# M101.net
KiCad netlist of a schematic drawn in EAGLE
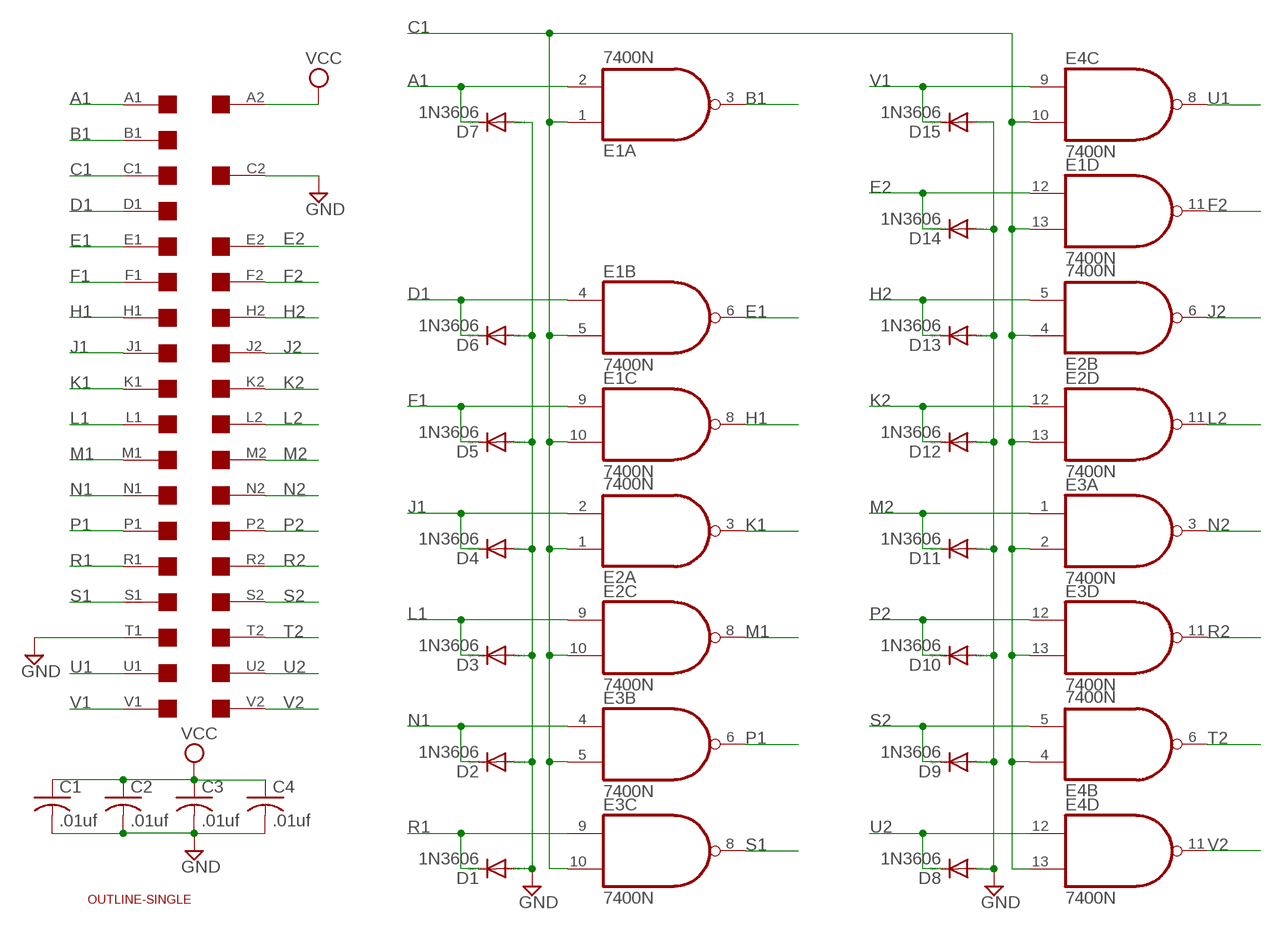
[diagram p0: schematic, sheet 1]

(export (version "E")
  (design (tool "Eeschema 10.0.6"))
  (components
    (comp (ref "C1")
      (value ".01uf")
      (footprint "eagle-import:C050-025X075")
      (libsource (lib "eagle-import") (part "C-US050-025X075"))
    )
    (comp (ref "C2")
      (value ".01uf")
      (footprint "eagle-import:C050-025X075")
      (libsource (lib "eagle-import") (part "C-US050-025X075"))
    )
    (comp (ref "C3")
      (value ".01uf")
      (footprint "eagle-import:C050-025X075")
      (libsource (lib "eagle-import") (part "C-US050-025X075"))
    )
    (comp (ref "C4")
      (value ".01uf")
      (footprint "eagle-import:C050-025X075")
      (libsource (lib "eagle-import") (part "C-US050-025X075"))
    )
    (comp (ref "D1")
      (value "1N3606")
      (footprint "eagle-import:DO35-10")
      (libsource (lib "eagle-import") (part "1N4148DO35-10"))
    )
    (comp (ref "D2")
      (value "1N3606")
      (footprint "eagle-import:DO35-10")
      (libsource (lib "eagle-import") (part "1N4148DO35-10"))
    )
    (comp (ref "D3")
      (value "1N3606")
      (footprint "eagle-import:DO35-10")
      (libsource (lib "eagle-import") (part "1N4148DO35-10"))
    )
    (comp (ref "D4")
      (value "1N3606")
      (footprint "eagle-import:DO35-10")
      (libsource (lib "eagle-import") (part "1N4148DO35-10"))
    )
    (comp (ref "D5")
      (value "1N3606")
      (footprint "eagle-import:DO35-10")
      (libsource (lib "eagle-import") (part "1N4148DO35-10"))
    )
    (comp (ref "D6")
      (value "1N3606")
      (footprint "eagle-import:DO35-10")
      (libsource (lib "eagle-import") (part "1N4148DO35-10"))
    )
    (comp (ref "D7")
      (value "1N3606")
      (footprint "eagle-import:DO35-10")
      (libsource (lib "eagle-import") (part "1N4148DO35-10"))
    )
    (comp (ref "D8")
      (value "1N3606")
      (footprint "eagle-import:DO35-10")
      (libsource (lib "eagle-import") (part "1N4148DO35-10"))
    )
    (comp (ref "D9")
      (value "1N3606")
      (footprint "eagle-import:DO35-10")
      (libsource (lib "eagle-import") (part "1N4148DO35-10"))
    )
    (comp (ref "D10")
      (value "1N3606")
      (footprint "eagle-import:DO35-10")
      (libsource (lib "eagle-import") (part "1N4148DO35-10"))
    )
    (comp (ref "D11")
      (value "1N3606")
      (footprint "eagle-import:DO35-10")
      (libsource (lib "eagle-import") (part "1N4148DO35-10"))
    )
    (comp (ref "D12")
      (value "1N3606")
      (footprint "eagle-import:DO35-10")
      (libsource (lib "eagle-import") (part "1N4148DO35-10"))
    )
    (comp (ref "D13")
      (value "1N3606")
      (footprint "eagle-import:DO35-10")
      (libsource (lib "eagle-import") (part "1N4148DO35-10"))
    )
    (comp (ref "D14")
      (value "1N3606")
      (footprint "eagle-import:DO35-10")
      (libsource (lib "eagle-import") (part "1N4148DO35-10"))
    )
    (comp (ref "D15")
      (value "1N3606")
      (footprint "eagle-import:DO35-10")
      (libsource (lib "eagle-import") (part "1N4148DO35-10"))
    )
    (comp (ref "E1")
      (value "7400N")
      (footprint "eagle-import:DIL14")
      (libsource (lib "eagle-import") (part "7400N"))
    )
    (comp (ref "E2")
      (value "7400N")
      (footprint "eagle-import:DIL14")
      (libsource (lib "eagle-import") (part "7400N"))
    )
    (comp (ref "E3")
      (value "7400N")
      (footprint "eagle-import:DIL14")
      (libsource (lib "eagle-import") (part "7400N"))
    )
    (comp (ref "E4")
      (value "7400N")
      (footprint "eagle-import:DIL14")
      (libsource (lib "eagle-import") (part "7400N"))
    )
    (comp (ref "U$1")
      (value "SINGLE")
      (footprint "eagle-import:EDGE-CON2")
      (libsource (lib "eagle-import") (part "SINGLE"))
    )
    (comp (ref "U$4")
      (value "OUTLINE-SINGLE")
      (footprint "eagle-import:SINGLE")
      (libsource (lib "eagle-import") (part "OUTLINE-SINGLE"))
    )
  )
  (nets
    (net (code "1") (name "/A1") (class "Default")
      (node (ref "D7") (pin "C") (pinfunction "C_C") (pintype "passive"))
      (node (ref "E1") (pin "2") (pinfunction "I1_2") (pintype "input"))
      (node (ref "U$1") (pin "A1") (pinfunction "1_A1") (pintype "bidirectional"))
    )
    (net (code "2") (name "/B1") (class "Default")
      (node (ref "E1") (pin "3") (pinfunction "O_3") (pintype "output"))
      (node (ref "U$1") (pin "B1") (pinfunction "1_B1") (pintype "bidirectional"))
    )
    (net (code "3") (name "/C1") (class "Default")
      (node (ref "E1") (pin "1") (pinfunction "I0_1") (pintype "input"))
      (node (ref "E1") (pin "10") (pinfunction "I1_10") (pintype "input"))
      (node (ref "E1") (pin "13") (pinfunction "I1_13") (pintype "input"))
      (node (ref "E1") (pin "5") (pinfunction "I1_5") (pintype "input"))
      (node (ref "E2") (pin "1") (pinfunction "I0_1") (pintype "input"))
      (node (ref "E2") (pin "10") (pinfunction "I1_10") (pintype "input"))
      (node (ref "E2") (pin "13") (pinfunction "I1_13") (pintype "input"))
      (node (ref "E2") (pin "4") (pinfunction "I0_4") (pintype "input"))
      (node (ref "E3") (pin "10") (pinfunction "I1_10") (pintype "input"))
      (node (ref "E3") (pin "13") (pinfunction "I1_13") (pintype "input"))
      (node (ref "E3") (pin "2") (pinfunction "I1_2") (pintype "input"))
      (node (ref "E3") (pin "5") (pinfunction "I1_5") (pintype "input"))
      (node (ref "E4") (pin "10") (pinfunction "I1_10") (pintype "input"))
      (node (ref "E4") (pin "13") (pinfunction "I1_13") (pintype "input"))
      (node (ref "E4") (pin "4") (pinfunction "I0_4") (pintype "input"))
      (node (ref "U$1") (pin "C1") (pinfunction "1_C1") (pintype "bidirectional"))
    )
    (net (code "4") (name "/D1") (class "Default")
      (node (ref "D6") (pin "C") (pinfunction "C_C") (pintype "passive"))
      (node (ref "E1") (pin "4") (pinfunction "I0_4") (pintype "input"))
      (node (ref "U$1") (pin "D1") (pinfunction "1_D1") (pintype "bidirectional"))
    )
    (net (code "5") (name "/E1") (class "Default")
      (node (ref "E1") (pin "6") (pinfunction "O_6") (pintype "output"))
      (node (ref "U$1") (pin "E1") (pinfunction "1_E1") (pintype "bidirectional"))
    )
    (net (code "6") (name "/E2") (class "Default")
      (node (ref "D14") (pin "C") (pinfunction "C_C") (pintype "passive"))
      (node (ref "E1") (pin "12") (pinfunction "I0_12") (pintype "input"))
      (node (ref "U$1") (pin "E2") (pinfunction "1_E2") (pintype "bidirectional"))
    )
    (net (code "7") (name "/F1") (class "Default")
      (node (ref "D5") (pin "C") (pinfunction "C_C") (pintype "passive"))
      (node (ref "E1") (pin "9") (pinfunction "I0_9") (pintype "input"))
      (node (ref "U$1") (pin "F1") (pinfunction "1_F1") (pintype "bidirectional"))
    )
    (net (code "8") (name "/F2") (class "Default")
      (node (ref "E1") (pin "11") (pinfunction "O_11") (pintype "output"))
      (node (ref "U$1") (pin "F2") (pinfunction "1_F2") (pintype "bidirectional"))
    )
    (net (code "9") (name "/H1") (class "Default")
      (node (ref "E1") (pin "8") (pinfunction "O_8") (pintype "output"))
      (node (ref "U$1") (pin "H1") (pinfunction "1_H1") (pintype "bidirectional"))
    )
    (net (code "10") (name "/H2") (class "Default")
      (node (ref "D13") (pin "C") (pinfunction "C_C") (pintype "passive"))
      (node (ref "E2") (pin "5") (pinfunction "I1_5") (pintype "input"))
      (node (ref "U$1") (pin "H2") (pinfunction "1_H2") (pintype "bidirectional"))
    )
    (net (code "11") (name "/J1") (class "Default")
      (node (ref "D4") (pin "C") (pinfunction "C_C") (pintype "passive"))
      (node (ref "E2") (pin "2") (pinfunction "I1_2") (pintype "input"))
      (node (ref "U$1") (pin "J1") (pinfunction "1_J1") (pintype "bidirectional"))
    )
    (net (code "12") (name "/J2") (class "Default")
      (node (ref "E2") (pin "6") (pinfunction "O_6") (pintype "output"))
      (node (ref "U$1") (pin "J2") (pinfunction "1_J2") (pintype "bidirectional"))
    )
    (net (code "13") (name "/K1") (class "Default")
      (node (ref "E2") (pin "3") (pinfunction "O_3") (pintype "output"))
      (node (ref "U$1") (pin "K1") (pinfunction "1_K1") (pintype "bidirectional"))
    )
    (net (code "14") (name "/K2") (class "Default")
      (node (ref "D12") (pin "C") (pinfunction "C_C") (pintype "passive"))
      (node (ref "E2") (pin "12") (pinfunction "I0_12") (pintype "input"))
      (node (ref "U$1") (pin "K2") (pinfunction "1_K2") (pintype "bidirectional"))
    )
    (net (code "15") (name "/L1") (class "Default")
      (node (ref "D3") (pin "C") (pinfunction "C_C") (pintype "passive"))
      (node (ref "E2") (pin "9") (pinfunction "I0_9") (pintype "input"))
      (node (ref "U$1") (pin "L1") (pinfunction "1_L1") (pintype "bidirectional"))
    )
    (net (code "16") (name "/L2") (class "Default")
      (node (ref "E2") (pin "11") (pinfunction "O_11") (pintype "output"))
      (node (ref "U$1") (pin "L2") (pinfunction "1_L2") (pintype "bidirectional"))
    )
    (net (code "17") (name "/M1") (class "Default")
      (node (ref "E2") (pin "8") (pinfunction "O_8") (pintype "output"))
      (node (ref "U$1") (pin "M1") (pinfunction "1_M1") (pintype "bidirectional"))
    )
    (net (code "18") (name "/M2") (class "Default")
      (node (ref "D11") (pin "C") (pinfunction "C_C") (pintype "passive"))
      (node (ref "E3") (pin "1") (pinfunction "I0_1") (pintype "input"))
      (node (ref "U$1") (pin "M2") (pinfunction "1_M2") (pintype "bidirectional"))
    )
    (net (code "19") (name "/N1") (class "Default")
      (node (ref "D2") (pin "C") (pinfunction "C_C") (pintype "passive"))
      (node (ref "E3") (pin "4") (pinfunction "I0_4") (pintype "input"))
      (node (ref "U$1") (pin "N1") (pinfunction "1_N1") (pintype "bidirectional"))
    )
    (net (code "20") (name "/N2") (class "Default")
      (node (ref "E3") (pin "3") (pinfunction "O_3") (pintype "output"))
      (node (ref "U$1") (pin "N2") (pinfunction "1_N2") (pintype "bidirectional"))
    )
    (net (code "21") (name "/P1") (class "Default")
      (node (ref "E3") (pin "6") (pinfunction "O_6") (pintype "output"))
      (node (ref "U$1") (pin "P1") (pinfunction "1_P1") (pintype "bidirectional"))
    )
    (net (code "22") (name "/P2") (class "Default")
      (node (ref "D10") (pin "C") (pinfunction "C_C") (pintype "passive"))
      (node (ref "E3") (pin "12") (pinfunction "I0_12") (pintype "input"))
      (node (ref "U$1") (pin "P2") (pinfunction "1_P2") (pintype "bidirectional"))
    )
    (net (code "23") (name "/R1") (class "Default")
      (node (ref "D1") (pin "C") (pinfunction "C_C") (pintype "passive"))
      (node (ref "E3") (pin "9") (pinfunction "I0_9") (pintype "input"))
      (node (ref "U$1") (pin "R1") (pinfunction "1_R1") (pintype "bidirectional"))
    )
    (net (code "24") (name "/R2") (class "Default")
      (node (ref "E3") (pin "11") (pinfunction "O_11") (pintype "output"))
      (node (ref "U$1") (pin "R2") (pinfunction "1_R2") (pintype "bidirectional"))
    )
    (net (code "25") (name "/S1") (class "Default")
      (node (ref "E3") (pin "8") (pinfunction "O_8") (pintype "output"))
      (node (ref "U$1") (pin "S1") (pinfunction "1_S1") (pintype "bidirectional"))
    )
    (net (code "26") (name "/S2") (class "Default")
      (node (ref "D9") (pin "C") (pinfunction "C_C") (pintype "passive"))
      (node (ref "E4") (pin "5") (pinfunction "I1_5") (pintype "input"))
      (node (ref "U$1") (pin "S2") (pinfunction "1_S2") (pintype "bidirectional"))
    )
    (net (code "27") (name "/T2") (class "Default")
      (node (ref "E4") (pin "6") (pinfunction "O_6") (pintype "output"))
      (node (ref "U$1") (pin "T2") (pinfunction "1_T2") (pintype "bidirectional"))
    )
    (net (code "28") (name "/U1") (class "Default")
      (node (ref "E4") (pin "8") (pinfunction "O_8") (pintype "output"))
      (node (ref "U$1") (pin "U1") (pinfunction "1_U1") (pintype "bidirectional"))
    )
    (net (code "29") (name "/U2") (class "Default")
      (node (ref "D8") (pin "C") (pinfunction "C_C") (pintype "passive"))
      (node (ref "E4") (pin "12") (pinfunction "I0_12") (pintype "input"))
      (node (ref "U$1") (pin "U2") (pinfunction "1_U2") (pintype "bidirectional"))
    )
    (net (code "30") (name "/V1") (class "Default")
      (node (ref "D15") (pin "C") (pinfunction "C_C") (pintype "passive"))
      (node (ref "E4") (pin "9") (pinfunction "I0_9") (pintype "input"))
      (node (ref "U$1") (pin "V1") (pinfunction "1_V1") (pintype "bidirectional"))
    )
    (net (code "31") (name "/V2") (class "Default")
      (node (ref "E4") (pin "11") (pinfunction "O_11") (pintype "output"))
      (node (ref "U$1") (pin "V2") (pinfunction "1_V2") (pintype "bidirectional"))
    )
    (net (code "32") (name "GND") (class "Default")
      (node (ref "C1") (pin "2") (pinfunction "2_2") (pintype "passive"))
      (node (ref "C2") (pin "2") (pinfunction "2_2") (pintype "passive"))
      (node (ref "C3") (pin "2") (pinfunction "2_2") (pintype "passive"))
      (node (ref "C4") (pin "2") (pinfunction "2_2") (pintype "passive"))
      (node (ref "D1") (pin "A") (pinfunction "A_A") (pintype "passive"))
      (node (ref "D10") (pin "A") (pinfunction "A_A") (pintype "passive"))
      (node (ref "D11") (pin "A") (pinfunction "A_A") (pintype "passive"))
      (node (ref "D12") (pin "A") (pinfunction "A_A") (pintype "passive"))
      (node (ref "D13") (pin "A") (pinfunction "A_A") (pintype "passive"))
      (node (ref "D14") (pin "A") (pinfunction "A_A") (pintype "passive"))
      (node (ref "D15") (pin "A") (pinfunction "A_A") (pintype "passive"))
      (node (ref "D2") (pin "A") (pinfunction "A_A") (pintype "passive"))
      (node (ref "D3") (pin "A") (pinfunction "A_A") (pintype "passive"))
      (node (ref "D4") (pin "A") (pinfunction "A_A") (pintype "passive"))
      (node (ref "D5") (pin "A") (pinfunction "A_A") (pintype "passive"))
      (node (ref "D6") (pin "A") (pinfunction "A_A") (pintype "passive"))
      (node (ref "D7") (pin "A") (pinfunction "A_A") (pintype "passive"))
      (node (ref "D8") (pin "A") (pinfunction "A_A") (pintype "passive"))
      (node (ref "D9") (pin "A") (pinfunction "A_A") (pintype "passive"))
      (node (ref "U$1") (pin "C2") (pinfunction "1_C2") (pintype "bidirectional"))
      (node (ref "U$1") (pin "T1") (pinfunction "1_T1") (pintype "bidirectional"))
    )
    (net (code "33") (name "VCC") (class "Default")
      (node (ref "C1") (pin "1") (pinfunction "1_1") (pintype "passive"))
      (node (ref "C2") (pin "1") (pinfunction "1_1") (pintype "passive"))
      (node (ref "C3") (pin "1") (pinfunction "1_1") (pintype "passive"))
      (node (ref "C4") (pin "1") (pinfunction "1_1") (pintype "passive"))
      (node (ref "U$1") (pin "A2") (pinfunction "1_A2") (pintype "bidirectional"))
    )
  )
)
